# DC48V_DC24V_200W_V1_0.net
KiCad netlist of a schematic drawn in Altium Designer
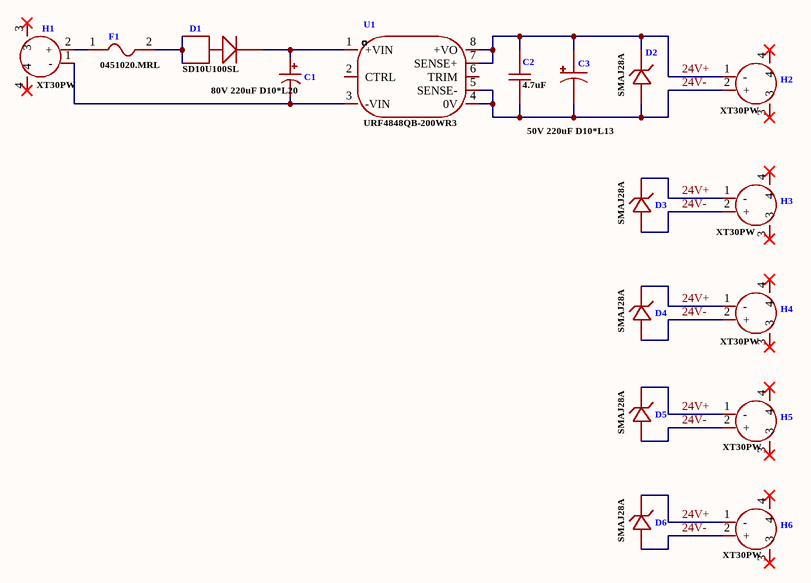
[diagram p0: DC48V_DC24V_200W_V1.0.SchDoc]

(export (version "E")
  (design (tool "Eeschema 10.0.6"))
  (components
    (comp (ref "C1")
      (value "80V 220uF D10*L20")
      (footprint "CAP-TH_BD10.0-P5.00-D1.0-FD-WL")
      (fields
        (field (name "MANUFACTURER") "AISHI(艾华集团)")
        (field (name "MANUFACTURER PART") "ERF1BM221G20OT")
        (field (name "TOLERANCE") "±20%")
      )
      (libsource (lib "电容") (part "ERF1BM221G20OT"))
    )
    (comp (ref "C2")
      (value "4.7uF")
      (footprint "1210_C")
      (description "100V 4.7uf 1210")
      (fields (field (name "MANUFACTURER") "FH(风华)") (field (name "MANUFACTURER PART") "1210B475K101NT"))
      (libsource (lib "Schlib1") (part "1210 4.7uf"))
    )
    (comp (ref "C3")
      (value "50V 220uF D10*L13")
      (footprint "CAP-TH_BD10.0-P5.00-D1.0-FD")
      (fields
        (field (name "MANUFACTURER") "AISHI(艾华集团)")
        (field (name "MANUFACTURER PART") "ERS1HM221G13OT")
        (field (name "TOLERANCE") "±20%")
      )
      (libsource (lib "电容") (part "ERS1HM221G13OT"))
    )
    (comp (ref "D1")
      (value "SD10U100SL")
      (footprint "TO-227B-SMD_L6.1-W4.3-LS7.0-RD")
      (fields (field (name "MANUFACTURER") "LGE(鲁光)"))
      (libsource (lib "二极管稳压等") (part "SD10U100SL"))
    )
    (comp (ref "D2")
      (value "SMAJ28A")
      (footprint "SMA_L4.4-W2.8-LS5.4-RD")
      (fields (field (name "MANUFACTURER") "Littelfuse(美国力特)"))
      (libsource (lib "二极管稳压等") (part "SMAJ28A_C148227"))
    )
    (comp (ref "D3")
      (value "SMAJ28A")
      (footprint "SMA_L4.4-W2.8-LS5.4-RD")
      (fields (field (name "MANUFACTURER") "Littelfuse(美国力特)"))
      (libsource (lib "二极管稳压等") (part "SMAJ28A_C148227"))
    )
    (comp (ref "D4")
      (value "SMAJ28A")
      (footprint "SMA_L4.4-W2.8-LS5.4-RD")
      (fields (field (name "MANUFACTURER") "Littelfuse(美国力特)"))
      (libsource (lib "二极管稳压等") (part "SMAJ28A_C148227"))
    )
    (comp (ref "D5")
      (value "SMAJ28A")
      (footprint "SMA_L4.4-W2.8-LS5.4-RD")
      (fields (field (name "MANUFACTURER") "Littelfuse(美国力特)"))
      (libsource (lib "二极管稳压等") (part "SMAJ28A_C148227"))
    )
    (comp (ref "D6")
      (value "SMAJ28A")
      (footprint "SMA_L4.4-W2.8-LS5.4-RD")
      (fields (field (name "MANUFACTURER") "Littelfuse(美国力特)"))
      (libsource (lib "二极管稳压等") (part "SMAJ28A_C148227"))
    )
    (comp (ref "F1")
      (value "0451020.MRL")
      (footprint "FUSE-SMD_L6.1-W2.7")
      (fields (field (name "MANUFACTURER") "Littelfuse(美国力特)"))
      (libsource (lib "保险") (part "0451020.MRL"))
    )
    (comp (ref "H1")
      (value "XT30PW")
      (footprint "CONN-TH_XT30PW-M")
      (fields (field (name "MANUFACTURER") "AMASS(艾迈斯)") (field (name "MANUFACTURER PART") "XT30PW-M30.G.Y"))
      (libsource (lib "Header") (part "XT30PW-M30.G.Y"))
    )
    (comp (ref "H2")
      (value "XT30PW")
      (footprint "CONN-TH_XT30PW-M")
      (fields (field (name "MANUFACTURER") "AMASS(艾迈斯)") (field (name "MANUFACTURER PART") "XT30PW-M30.G.Y"))
      (libsource (lib "Header") (part "XT30PW-M30.G.Y"))
    )
    (comp (ref "H3")
      (value "XT30PW")
      (footprint "CONN-TH_XT30PW-M")
      (fields (field (name "MANUFACTURER") "AMASS(艾迈斯)") (field (name "MANUFACTURER PART") "XT30PW-M30.G.Y"))
      (libsource (lib "Header") (part "XT30PW-M30.G.Y"))
    )
    (comp (ref "H4")
      (value "XT30PW")
      (footprint "CONN-TH_XT30PW-M")
      (fields (field (name "MANUFACTURER") "AMASS(艾迈斯)") (field (name "MANUFACTURER PART") "XT30PW-M30.G.Y"))
      (libsource (lib "Header") (part "XT30PW-M30.G.Y"))
    )
    (comp (ref "H5")
      (value "XT30PW")
      (footprint "CONN-TH_XT30PW-M")
      (fields (field (name "MANUFACTURER") "AMASS(艾迈斯)") (field (name "MANUFACTURER PART") "XT30PW-M30.G.Y"))
      (libsource (lib "Header") (part "XT30PW-M30.G.Y"))
    )
    (comp (ref "H6")
      (value "XT30PW")
      (footprint "CONN-TH_XT30PW-M")
      (fields (field (name "MANUFACTURER") "AMASS(艾迈斯)") (field (name "MANUFACTURER PART") "XT30PW-M30.G.Y"))
      (libsource (lib "Header") (part "XT30PW-M30.G.Y"))
    )
    (comp (ref "U1")
      (value "URF4848QB-200WR3")
      (footprint "PWRM-TH_URF48XXQB-200WR3")
      (fields (field (name "MANUFACTURER") "MORNSUN(金升阳)"))
      (libsource (lib "电源及控制") (part "URF4848QB-200WR3"))
    )
  )
  (nets
    (net (code "1") (name "/24V+") (class "Default")
      (node (ref "C2") (pin "2") (pinfunction "2_2") (pintype "passive"))
      (node (ref "C3") (pin "1") (pinfunction "1_1") (pintype "passive"))
      (node (ref "D2") (pin "1") (pinfunction "1_1") (pintype "passive"))
      (node (ref "D3") (pin "1") (pinfunction "1_1") (pintype "passive"))
      (node (ref "D4") (pin "1") (pinfunction "1_1") (pintype "passive"))
      (node (ref "D5") (pin "1") (pinfunction "1_1") (pintype "passive"))
      (node (ref "D6") (pin "1") (pinfunction "1_1") (pintype "passive"))
      (node (ref "H2") (pin "1") (pinfunction "-_1") (pintype "passive"))
      (node (ref "H3") (pin "1") (pinfunction "-_1") (pintype "passive"))
      (node (ref "H4") (pin "1") (pinfunction "-_1") (pintype "passive"))
      (node (ref "H5") (pin "1") (pinfunction "-_1") (pintype "passive"))
      (node (ref "H6") (pin "1") (pinfunction "-_1") (pintype "passive"))
      (node (ref "U1") (pin "7") (pinfunction "SENSE+_7") (pintype "passive"))
      (node (ref "U1") (pin "8") (pinfunction "+VO_8") (pintype "passive"))
    )
    (net (code "2") (name "/24V-") (class "Default")
      (node (ref "C2") (pin "1") (pinfunction "1_1") (pintype "passive"))
      (node (ref "C3") (pin "2") (pinfunction "2_2") (pintype "passive"))
      (node (ref "D2") (pin "2") (pinfunction "2_2") (pintype "passive"))
      (node (ref "D3") (pin "2") (pinfunction "2_2") (pintype "passive"))
      (node (ref "D4") (pin "2") (pinfunction "2_2") (pintype "passive"))
      (node (ref "D5") (pin "2") (pinfunction "2_2") (pintype "passive"))
      (node (ref "D6") (pin "2") (pinfunction "2_2") (pintype "passive"))
      (node (ref "H2") (pin "2") (pinfunction "+_2") (pintype "passive"))
      (node (ref "H3") (pin "2") (pinfunction "+_2") (pintype "passive"))
      (node (ref "H4") (pin "2") (pinfunction "+_2") (pintype "passive"))
      (node (ref "H5") (pin "2") (pinfunction "+_2") (pintype "passive"))
      (node (ref "H6") (pin "2") (pinfunction "+_2") (pintype "passive"))
      (node (ref "U1") (pin "4") (pinfunction "0V_4") (pintype "passive"))
      (node (ref "U1") (pin "5") (pinfunction "SENSE-_5") (pintype "passive"))
    )
    (net (code "3") (name "Net-(D1-Pad1)") (class "Default")
      (node (ref "D1") (pin "1") (pinfunction "1_1") (pintype "passive"))
      (node (ref "D1") (pin "2") (pinfunction "2_2") (pintype "passive"))
      (node (ref "F1") (pin "2") (pinfunction "2_2") (pintype "passive"))
    )
    (net (code "4") (name "Net-(H1-+)") (class "Default")
      (node (ref "F1") (pin "1") (pinfunction "1_1") (pintype "passive"))
      (node (ref "H1") (pin "2") (pinfunction "+_2") (pintype "passive"))
    )
    (net (code "5") (name "Net-(H1--)") (class "Default")
      (node (ref "C1") (pin "2") (pinfunction "2_2") (pintype "passive"))
      (node (ref "H1") (pin "1") (pinfunction "-_1") (pintype "passive"))
      (node (ref "U1") (pin "3") (pinfunction "-VIN_3") (pintype "passive"))
    )
    (net (code "6") (name "Net-(U1-+VIN)") (class "Default")
      (node (ref "C1") (pin "1") (pinfunction "1_1") (pintype "passive"))
      (node (ref "D1") (pin "3") (pinfunction "3_3") (pintype "passive"))
      (node (ref "U1") (pin "1") (pinfunction "+VIN_1") (pintype "passive"))
    )
    (net (code "7") (name "unconnected-(H1-Pad3)") (class "Default")
      (node (ref "H1") (pin "3") (pinfunction "3_3") (pintype "passive+no_connect"))
    )
    (net (code "8") (name "unconnected-(H1-Pad4)") (class "Default")
      (node (ref "H1") (pin "4") (pinfunction "4_4") (pintype "passive+no_connect"))
    )
    (net (code "9") (name "unconnected-(H2-Pad3)") (class "Default")
      (node (ref "H2") (pin "3") (pinfunction "3_3") (pintype "passive+no_connect"))
    )
    (net (code "10") (name "unconnected-(H2-Pad4)") (class "Default")
      (node (ref "H2") (pin "4") (pinfunction "4_4") (pintype "passive+no_connect"))
    )
    (net (code "11") (name "unconnected-(H3-Pad3)") (class "Default")
      (node (ref "H3") (pin "3") (pinfunction "3_3") (pintype "passive+no_connect"))
    )
    (net (code "12") (name "unconnected-(H3-Pad4)") (class "Default")
      (node (ref "H3") (pin "4") (pinfunction "4_4") (pintype "passive+no_connect"))
    )
    (net (code "13") (name "unconnected-(H4-Pad3)") (class "Default")
      (node (ref "H4") (pin "3") (pinfunction "3_3") (pintype "passive+no_connect"))
    )
    (net (code "14") (name "unconnected-(H4-Pad4)") (class "Default")
      (node (ref "H4") (pin "4") (pinfunction "4_4") (pintype "passive+no_connect"))
    )
    (net (code "15") (name "unconnected-(H5-Pad3)") (class "Default")
      (node (ref "H5") (pin "3") (pinfunction "3_3") (pintype "passive+no_connect"))
    )
    (net (code "16") (name "unconnected-(H5-Pad4)") (class "Default")
      (node (ref "H5") (pin "4") (pinfunction "4_4") (pintype "passive+no_connect"))
    )
    (net (code "17") (name "unconnected-(H6-Pad3)") (class "Default")
      (node (ref "H6") (pin "3") (pinfunction "3_3") (pintype "passive+no_connect"))
    )
    (net (code "18") (name "unconnected-(H6-Pad4)") (class "Default")
      (node (ref "H6") (pin "4") (pinfunction "4_4") (pintype "passive+no_connect"))
    )
    (net (code "19") (name "unconnected-(U1-CTRL-Pad2)") (class "Default")
      (node (ref "U1") (pin "2") (pinfunction "CTRL_2") (pintype "passive"))
    )
    (net (code "20") (name "unconnected-(U1-TRIM-Pad6)") (class "Default")
      (node (ref "U1") (pin "6") (pinfunction "TRIM_6") (pintype "passive"))
    )
  )
)
